# PCA9548ABreakout.net
KiCad netlist of a schematic drawn in EAGLE
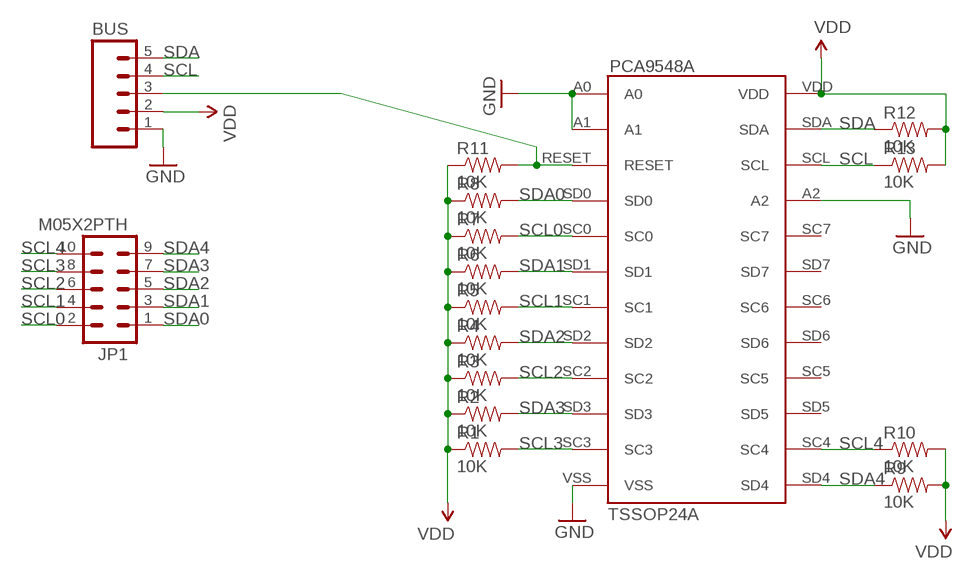
[diagram p0: schematic, sheet 1]

(export (version "E")
  (design (tool "Eeschema 10.0.6"))
  (components
    (comp (ref "BUS")
      (value "M05PTH")
      (footprint "eagle-import:1X05")
      (libsource (lib "eagle-import") (part "M05PTH"))
    )
    (comp (ref "JP1")
      (value "M05X2PTH")
      (footprint "eagle-import:AVR_ICSP")
      (libsource (lib "eagle-import") (part "M05X2PTH"))
    )
    (comp (ref "PCA9548A")
      (value "TSSOP24A")
      (footprint "eagle-import:TSSOP24")
      (libsource (lib "eagle-import") (part "TSSOP24A"))
    )
    (comp (ref "R1")
      (value "10K")
      (footprint "eagle-import:0603-RES")
      (libsource (lib "eagle-import") (part "10KOHM1/10W1%(0603)0603"))
    )
    (comp (ref "R2")
      (value "10K")
      (footprint "eagle-import:0603-RES")
      (libsource (lib "eagle-import") (part "10KOHM1/10W1%(0603)0603"))
    )
    (comp (ref "R3")
      (value "10K")
      (footprint "eagle-import:0603-RES")
      (libsource (lib "eagle-import") (part "10KOHM1/10W1%(0603)0603"))
    )
    (comp (ref "R4")
      (value "10K")
      (footprint "eagle-import:0603-RES")
      (libsource (lib "eagle-import") (part "10KOHM1/10W1%(0603)0603"))
    )
    (comp (ref "R5")
      (value "10K")
      (footprint "eagle-import:0603-RES")
      (libsource (lib "eagle-import") (part "10KOHM1/10W1%(0603)0603"))
    )
    (comp (ref "R6")
      (value "10K")
      (footprint "eagle-import:0603-RES")
      (libsource (lib "eagle-import") (part "10KOHM1/10W1%(0603)0603"))
    )
    (comp (ref "R7")
      (value "10K")
      (footprint "eagle-import:0603-RES")
      (libsource (lib "eagle-import") (part "10KOHM1/10W1%(0603)0603"))
    )
    (comp (ref "R8")
      (value "10K")
      (footprint "eagle-import:0603-RES")
      (libsource (lib "eagle-import") (part "10KOHM1/10W1%(0603)0603"))
    )
    (comp (ref "R9")
      (value "10K")
      (footprint "eagle-import:0603-RES")
      (libsource (lib "eagle-import") (part "10KOHM1/10W1%(0603)0603"))
    )
    (comp (ref "R10")
      (value "10K")
      (footprint "eagle-import:0603-RES")
      (libsource (lib "eagle-import") (part "10KOHM1/10W1%(0603)0603"))
    )
    (comp (ref "R11")
      (value "10K")
      (footprint "eagle-import:0603-RES")
      (libsource (lib "eagle-import") (part "10KOHM1/10W1%(0603)0603"))
    )
    (comp (ref "R12")
      (value "10K")
      (footprint "eagle-import:0603-RES")
      (libsource (lib "eagle-import") (part "10KOHM1/10W1%(0603)0603"))
    )
    (comp (ref "R13")
      (value "10K")
      (footprint "eagle-import:0603-RES")
      (libsource (lib "eagle-import") (part "10KOHM1/10W1%(0603)0603"))
    )
  )
  (nets
    (net (code "1") (name "/SCL") (class "Default")
      (node (ref "BUS") (pin "4") (pinfunction "4_4") (pintype "passive"))
      (node (ref "PCA9548A") (pin "SCL") (pinfunction "SCL_SCL") (pintype "bidirectional"))
      (node (ref "R13") (pin "1") (pinfunction "1_1") (pintype "passive"))
    )
    (net (code "2") (name "/SCL0") (class "Default")
      (node (ref "JP1") (pin "2") (pinfunction "2_2") (pintype "passive"))
      (node (ref "PCA9548A") (pin "SC0") (pinfunction "SC0_SC0") (pintype "bidirectional"))
      (node (ref "R7") (pin "2") (pinfunction "2_2") (pintype "passive"))
    )
    (net (code "3") (name "/SCL1") (class "Default")
      (node (ref "JP1") (pin "4") (pinfunction "4_4") (pintype "passive"))
      (node (ref "PCA9548A") (pin "SC1") (pinfunction "SC1_SC1") (pintype "bidirectional"))
      (node (ref "R5") (pin "2") (pinfunction "2_2") (pintype "passive"))
    )
    (net (code "4") (name "/SCL2") (class "Default")
      (node (ref "JP1") (pin "6") (pinfunction "6_6") (pintype "passive"))
      (node (ref "PCA9548A") (pin "SC2") (pinfunction "SC2_SC2") (pintype "bidirectional"))
      (node (ref "R3") (pin "2") (pinfunction "2_2") (pintype "passive"))
    )
    (net (code "5") (name "/SCL3") (class "Default")
      (node (ref "JP1") (pin "8") (pinfunction "8_8") (pintype "passive"))
      (node (ref "PCA9548A") (pin "SC3") (pinfunction "SC3_SC3") (pintype "bidirectional"))
      (node (ref "R1") (pin "2") (pinfunction "2_2") (pintype "passive"))
    )
    (net (code "6") (name "/SCL4") (class "Default")
      (node (ref "JP1") (pin "10") (pinfunction "10_10") (pintype "passive"))
      (node (ref "PCA9548A") (pin "SC4") (pinfunction "SC4_SC4") (pintype "bidirectional"))
      (node (ref "R10") (pin "1") (pinfunction "1_1") (pintype "passive"))
    )
    (net (code "7") (name "/SDA") (class "Default")
      (node (ref "BUS") (pin "5") (pinfunction "5_5") (pintype "passive"))
      (node (ref "PCA9548A") (pin "SDA") (pinfunction "SDA_SDA") (pintype "bidirectional"))
      (node (ref "R12") (pin "1") (pinfunction "1_1") (pintype "passive"))
    )
    (net (code "8") (name "/SDA0") (class "Default")
      (node (ref "JP1") (pin "1") (pinfunction "1_1") (pintype "passive"))
      (node (ref "PCA9548A") (pin "SD0") (pinfunction "SD0_SD0") (pintype "bidirectional"))
      (node (ref "R8") (pin "2") (pinfunction "2_2") (pintype "passive"))
    )
    (net (code "9") (name "/SDA1") (class "Default")
      (node (ref "JP1") (pin "3") (pinfunction "3_3") (pintype "passive"))
      (node (ref "PCA9548A") (pin "SD1") (pinfunction "SD1_SD1") (pintype "bidirectional"))
      (node (ref "R6") (pin "2") (pinfunction "2_2") (pintype "passive"))
    )
    (net (code "10") (name "/SDA2") (class "Default")
      (node (ref "JP1") (pin "5") (pinfunction "5_5") (pintype "passive"))
      (node (ref "PCA9548A") (pin "SD2") (pinfunction "SD2_SD2") (pintype "bidirectional"))
      (node (ref "R4") (pin "2") (pinfunction "2_2") (pintype "passive"))
    )
    (net (code "11") (name "/SDA3") (class "Default")
      (node (ref "JP1") (pin "7") (pinfunction "7_7") (pintype "passive"))
      (node (ref "PCA9548A") (pin "SD3") (pinfunction "SD3_SD3") (pintype "bidirectional"))
      (node (ref "R2") (pin "2") (pinfunction "2_2") (pintype "passive"))
    )
    (net (code "12") (name "/SDA4") (class "Default")
      (node (ref "JP1") (pin "9") (pinfunction "9_9") (pintype "passive"))
      (node (ref "PCA9548A") (pin "SD4") (pinfunction "SD4_SD4") (pintype "bidirectional"))
      (node (ref "R9") (pin "1") (pinfunction "1_1") (pintype "passive"))
    )
    (net (code "13") (name "GND") (class "Default")
      (node (ref "BUS") (pin "1") (pinfunction "1_1") (pintype "passive"))
      (node (ref "PCA9548A") (pin "A0") (pinfunction "A0_A0") (pintype "bidirectional"))
      (node (ref "PCA9548A") (pin "A1") (pinfunction "A1_A1") (pintype "bidirectional"))
      (node (ref "PCA9548A") (pin "A2") (pinfunction "A2_A2") (pintype "bidirectional"))
      (node (ref "PCA9548A") (pin "VSS") (pinfunction "VSS_VSS") (pintype "bidirectional"))
    )
    (net (code "14") (name "Net-(BUS-Pad3)") (class "Default")
      (node (ref "BUS") (pin "3") (pinfunction "3_3") (pintype "passive"))
      (node (ref "PCA9548A") (pin "RESET") (pinfunction "RESET_RESET") (pintype "bidirectional"))
      (node (ref "R11") (pin "2") (pinfunction "2_2") (pintype "passive"))
    )
    (net (code "15") (name "VDD") (class "Default")
      (node (ref "BUS") (pin "2") (pinfunction "2_2") (pintype "passive"))
      (node (ref "PCA9548A") (pin "VDD") (pinfunction "VDD_VDD") (pintype "bidirectional"))
      (node (ref "R1") (pin "1") (pinfunction "1_1") (pintype "passive"))
      (node (ref "R10") (pin "2") (pinfunction "2_2") (pintype "passive"))
      (node (ref "R11") (pin "1") (pinfunction "1_1") (pintype "passive"))
      (node (ref "R12") (pin "2") (pinfunction "2_2") (pintype "passive"))
      (node (ref "R13") (pin "2") (pinfunction "2_2") (pintype "passive"))
      (node (ref "R2") (pin "1") (pinfunction "1_1") (pintype "passive"))
      (node (ref "R3") (pin "1") (pinfunction "1_1") (pintype "passive"))
      (node (ref "R4") (pin "1") (pinfunction "1_1") (pintype "passive"))
      (node (ref "R5") (pin "1") (pinfunction "1_1") (pintype "passive"))
      (node (ref "R6") (pin "1") (pinfunction "1_1") (pintype "passive"))
      (node (ref "R7") (pin "1") (pinfunction "1_1") (pintype "passive"))
      (node (ref "R8") (pin "1") (pinfunction "1_1") (pintype "passive"))
      (node (ref "R9") (pin "2") (pinfunction "2_2") (pintype "passive"))
    )
    (net (code "16") (name "unconnected-(PCA9548A-PadSC5)") (class "Default")
      (node (ref "PCA9548A") (pin "SC5") (pinfunction "SC5_SC5") (pintype "bidirectional"))
    )
    (net (code "17") (name "unconnected-(PCA9548A-PadSC6)") (class "Default")
      (node (ref "PCA9548A") (pin "SC6") (pinfunction "SC6_SC6") (pintype "bidirectional"))
    )
    (net (code "18") (name "unconnected-(PCA9548A-PadSC7)") (class "Default")
      (node (ref "PCA9548A") (pin "SC7") (pinfunction "SC7_SC7") (pintype "bidirectional"))
    )
    (net (code "19") (name "unconnected-(PCA9548A-PadSD5)") (class "Default")
      (node (ref "PCA9548A") (pin "SD5") (pinfunction "SD5_SD5") (pintype "bidirectional"))
    )
    (net (code "20") (name "unconnected-(PCA9548A-PadSD6)") (class "Default")
      (node (ref "PCA9548A") (pin "SD6") (pinfunction "SD6_SD6") (pintype "bidirectional"))
    )
    (net (code "21") (name "unconnected-(PCA9548A-PadSD7)") (class "Default")
      (node (ref "PCA9548A") (pin "SD7") (pinfunction "SD7_SD7") (pintype "bidirectional"))
    )
  )
)
